# Atmega328p.net
KiCad netlist of a schematic drawn in Altium Designer
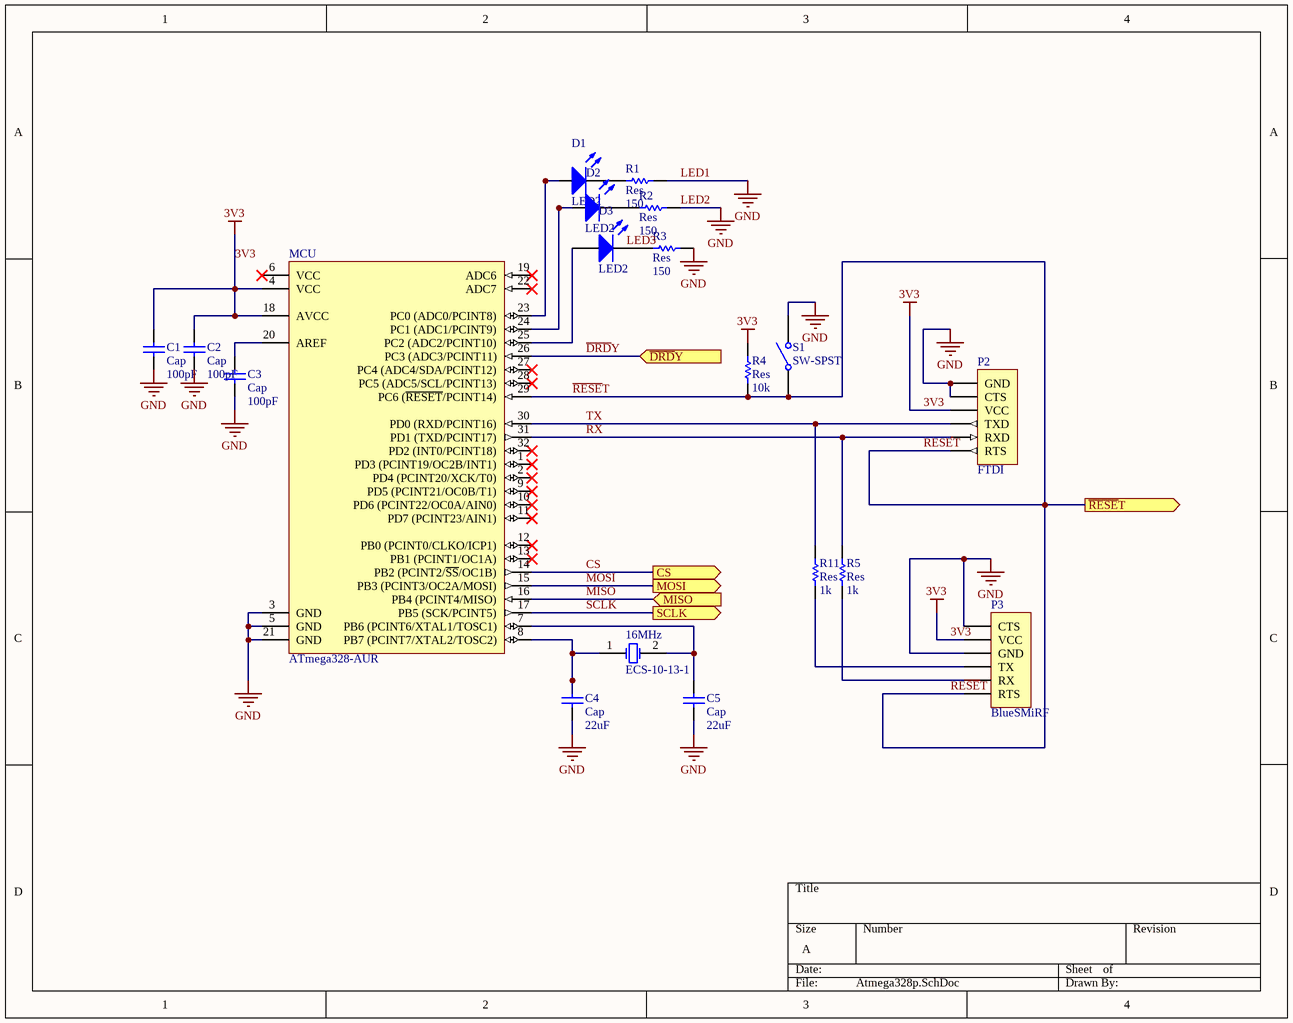
[diagram p0: Atmega328p.SchDoc]

(export (version "E")
  (design (tool "Eeschema 10.0.6"))
  (components
    (comp (ref "16MHz")
      (value "ECS-10-13-1")
      (footprint "HC-49U")
      (description "Crystal Oscillator")
      (fields (field (name "PUBLISHER") "Altium Limited"))
      (libsource (lib "ECS Crystal Oscillator") (part "ECS-10-13-1"))
    )
    (comp (ref "C1")
      (value "Cap")
      (footprint "1608[0603]")
      (description "Capacitor")
      (fields (field (name "C1") "100pF") (field (name "PUBLISHER") "Altium Limited"))
      (libsource (lib "Miscellaneous Devices") (part "Cap"))
    )
    (comp (ref "C2")
      (value "Cap")
      (footprint "1608[0603]")
      (description "Capacitor")
      (fields (field (name "C1") "100pF") (field (name "PUBLISHER") "Altium Limited"))
      (libsource (lib "Miscellaneous Devices") (part "Cap"))
    )
    (comp (ref "C3")
      (value "Cap")
      (footprint "1608[0603]")
      (description "Capacitor")
      (fields (field (name "C1") "100pF") (field (name "PUBLISHER") "Altium Limited"))
      (libsource (lib "Miscellaneous Devices") (part "Cap"))
    )
    (comp (ref "C4")
      (value "Cap")
      (footprint "1608[0603]")
      (description "Capacitor")
      (fields (field (name "ALTIUM_VALUE") "22uF") (field (name "PUBLISHER") "Altium Limited"))
      (libsource (lib "Miscellaneous Devices") (part "Cap"))
    )
    (comp (ref "C5")
      (value "Cap")
      (footprint "1608[0603]")
      (description "Capacitor")
      (fields (field (name "ALTIUM_VALUE") "22uF") (field (name "PUBLISHER") "Altium Limited"))
      (libsource (lib "Miscellaneous Devices") (part "Cap"))
    )
    (comp (ref "D1")
      (value "LED2")
      (footprint "3.2X1.6X1.1")
      (description "Typical RED, GREEN, YELLOW, AMBER GaAs LED")
      (fields (field (name "PUBLISHER") "Altium Limited"))
      (libsource (lib "Miscellaneous Devices") (part "LED2"))
    )
    (comp (ref "D2")
      (value "LED2")
      (footprint "3.2X1.6X1.1")
      (description "Typical RED, GREEN, YELLOW, AMBER GaAs LED")
      (fields (field (name "PUBLISHER") "Altium Limited"))
      (libsource (lib "Miscellaneous Devices") (part "LED2"))
    )
    (comp (ref "D3")
      (value "LED2")
      (footprint "3.2X1.6X1.1")
      (description "Typical RED, GREEN, YELLOW, AMBER GaAs LED")
      (fields (field (name "PUBLISHER") "Altium Limited"))
      (libsource (lib "Miscellaneous Devices") (part "LED2"))
    )
    (comp (ref "MCU")
      (value "ATmega328-AUR")
      (footprint "32A_N")
      (fields (field (name "PUBLISHER") "Altium Limited"))
      (libsource (lib "Atmel Microcontroller 8-Bit megaAVR") (part "ATmega328-AUR"))
    )
    (comp (ref "P2")
      (value "FTDI")
      (footprint "HDR1X6")
      (description "Header, 6-Pin")
      (fields (field (name "PUBLISHER") "Altium Limited"))
      (libsource (lib "Miscellaneous Connectors") (part "Header 6"))
    )
    (comp (ref "P3")
      (value "BlueSMiRF")
      (footprint "HDR1X6")
      (description "Header, 6-Pin")
      (fields (field (name "PUBLISHER") "Altium Limited"))
      (libsource (lib "Miscellaneous Connectors") (part "Header 6"))
    )
    (comp (ref "R1")
      (value "Res")
      (footprint "1608[0603]")
      (description "Resistor")
      (fields (field (name "ALTIUM_VALUE") "150") (field (name "PUBLISHER") "Altium Limited"))
      (libsource (lib "Miscellaneous Devices") (part "Res1"))
    )
    (comp (ref "R2")
      (value "Res")
      (footprint "1608[0603]")
      (description "Resistor")
      (fields (field (name "ALTIUM_VALUE") "150") (field (name "PUBLISHER") "Altium Limited"))
      (libsource (lib "Miscellaneous Devices") (part "Res1"))
    )
    (comp (ref "R3")
      (value "Res")
      (footprint "1608[0603]")
      (description "Resistor")
      (fields (field (name "ALTIUM_VALUE") "150") (field (name "PUBLISHER") "Altium Limited"))
      (libsource (lib "Miscellaneous Devices") (part "Res1"))
    )
    (comp (ref "R4")
      (value "Res")
      (footprint "J1-0603")
      (description "Resistor")
      (fields (field (name "ALTIUM_VALUE") "10k") (field (name "PUBLISHER") "Altium Limited"))
      (libsource (lib "Miscellaneous Devices") (part "Res1"))
    )
    (comp (ref "R5")
      (value "Res")
      (footprint "1608[0603]")
      (description "Resistor")
      (fields (field (name "ALTIUM_VALUE") "1k") (field (name "PUBLISHER") "Altium Limited"))
      (libsource (lib "Miscellaneous Devices") (part "Res1"))
    )
    (comp (ref "R11")
      (value "Res")
      (footprint "1608[0603]")
      (description "Resistor")
      (fields (field (name "ALTIUM_VALUE") "1k") (field (name "PUBLISHER") "Altium Limited"))
      (libsource (lib "Miscellaneous Devices") (part "Res1"))
    )
    (comp (ref "S1")
      (value "SW-SPST")
      (footprint "SPST-2")
      (description "Single-Pole, Single-Throw Switch")
      (fields (field (name "PUBLISHER") "Altium Limited"))
      (libsource (lib "Miscellaneous Devices") (part "SW-SPST"))
    )
  )
  (nets
    (net (code "1") (name "/CS") (class "Default")
      (node (ref "MCU") (pin "14") (pinfunction "PB2_(PCINT2/~{SS}/OC1B)_14") (pintype "output"))
    )
    (net (code "3") (name "/MISO") (class "Default")
      (node (ref "MCU") (pin "16") (pinfunction "PB4_(PCINT4/MISO)_16") (pintype "input"))
    )
    (net (code "4") (name "/MOSI") (class "Default")
      (node (ref "MCU") (pin "15") (pinfunction "PB3_(PCINT3/OC2A/MOSI)_15") (pintype "output"))
    )
    (net (code "5") (name "/RX") (class "Default")
      (node (ref "MCU") (pin "31") (pinfunction "PD1_(TXD/PCINT17)_31") (pintype "output"))
      (node (ref "P2") (pin "5") (pinfunction "RXD_5") (pintype "input"))
      (node (ref "R5") (pin "1") (pinfunction "1_1") (pintype "passive"))
    )
    (net (code "6") (name "/SCLK") (class "Default")
      (node (ref "MCU") (pin "17") (pinfunction "PB5_(SCK/PCINT5)_17") (pintype "output"))
    )
    (net (code "7") (name "/TX") (class "Default")
      (node (ref "MCU") (pin "30") (pinfunction "PD0_(RXD/PCINT16)_30") (pintype "input"))
      (node (ref "P2") (pin "4") (pinfunction "TXD_4") (pintype "output"))
      (node (ref "R11") (pin "1") (pinfunction "1_1") (pintype "passive"))
    )
    (net (code "8") (name "/~{DRD}Y") (class "Default")
      (node (ref "MCU") (pin "26") (pinfunction "PC3_(ADC3/PCINT11)_26") (pintype "input"))
    )
    (net (code "9") (name "/~{RESE}T") (class "Default")
      (node (ref "MCU") (pin "29") (pinfunction "PC6_(~{RESET}/PCINT14)_29") (pintype "input"))
      (node (ref "P2") (pin "6") (pinfunction "RTS_6") (pintype "output"))
      (node (ref "P3") (pin "6") (pinfunction "RTS_6") (pintype "output"))
      (node (ref "R4") (pin "1") (pinfunction "1_1") (pintype "passive"))
      (node (ref "S1") (pin "1") (pinfunction "COMMON_1") (pintype "passive"))
    )
    (net (code "10") (name "3V3") (class "Default")
      (node (ref "C1") (pin "2") (pinfunction "2_2") (pintype "passive"))
      (node (ref "C2") (pin "2") (pinfunction "2_2") (pintype "passive"))
      (node (ref "MCU") (pin "18") (pinfunction "AVCC_18") (pintype "power_in"))
      (node (ref "MCU") (pin "4") (pinfunction "VCC_4") (pintype "power_in"))
      (node (ref "P2") (pin "3") (pinfunction "VCC_3") (pintype "power_in"))
      (node (ref "P3") (pin "2") (pinfunction "CTS_2") (pintype "passive"))
      (node (ref "R4") (pin "2") (pinfunction "2_2") (pintype "passive"))
    )
    (net (code "11") (name "GND") (class "Default")
      (node (ref "C1") (pin "1") (pinfunction "1_1") (pintype "passive"))
      (node (ref "C2") (pin "1") (pinfunction "1_1") (pintype "passive"))
      (node (ref "C3") (pin "1") (pinfunction "1_1") (pintype "passive"))
      (node (ref "C4") (pin "1") (pinfunction "1_1") (pintype "passive"))
      (node (ref "C5") (pin "1") (pinfunction "1_1") (pintype "passive"))
      (node (ref "MCU") (pin "21") (pinfunction "GND_21") (pintype "power_in"))
      (node (ref "MCU") (pin "3") (pinfunction "GND_3") (pintype "power_in"))
      (node (ref "MCU") (pin "5") (pinfunction "GND_5") (pintype "power_in"))
      (node (ref "P2") (pin "1") (pinfunction "GND_1") (pintype "power_in"))
      (node (ref "P2") (pin "2") (pinfunction "CTS_2") (pintype "passive"))
      (node (ref "P3") (pin "1") (pinfunction "GND_1") (pintype "power_in"))
      (node (ref "P3") (pin "3") (pinfunction "VCC_3") (pintype "power_in"))
      (node (ref "R1") (pin "1") (pinfunction "1_1") (pintype "passive"))
      (node (ref "R2") (pin "1") (pinfunction "1_1") (pintype "passive"))
      (node (ref "R3") (pin "1") (pinfunction "1_1") (pintype "passive"))
      (node (ref "S1") (pin "2") (pinfunction "NO_2") (pintype "passive"))
    )
    (net (code "12") (name "Net-(16MHz-OSC1)") (class "Default")
      (node (ref "16MHz") (pin "1") (pinfunction "OSC1_1") (pintype "passive"))
      (node (ref "C4") (pin "2") (pinfunction "2_2") (pintype "passive"))
      (node (ref "MCU") (pin "8") (pinfunction "PB7_(PCINT7/XTAL2/TOSC2)_8") (pintype "bidirectional"))
    )
    (net (code "13") (name "Net-(16MHz-OSC2)") (class "Default")
      (node (ref "16MHz") (pin "2") (pinfunction "OSC2_2") (pintype "passive"))
      (node (ref "C5") (pin "2") (pinfunction "2_2") (pintype "passive"))
      (node (ref "MCU") (pin "7") (pinfunction "PB6_(PCINT6/XTAL1/TOSC1)_7") (pintype "bidirectional"))
    )
    (net (code "14") (name "Net-(D1-A)") (class "Default")
      (node (ref "D1") (pin "1") (pinfunction "A_1") (pintype "passive"))
      (node (ref "MCU") (pin "23") (pinfunction "PC0_(ADC0/PCINT8)_23") (pintype "bidirectional"))
    )
    (net (code "15") (name "Net-(D1-K)") (class "Default")
      (node (ref "D1") (pin "2") (pinfunction "K_2") (pintype "passive"))
      (node (ref "R1") (pin "2") (pinfunction "2_2") (pintype "passive"))
    )
    (net (code "16") (name "Net-(D2-A)") (class "Default")
      (node (ref "D2") (pin "1") (pinfunction "A_1") (pintype "passive"))
      (node (ref "MCU") (pin "24") (pinfunction "PC1_(ADC1/PCINT9)_24") (pintype "bidirectional"))
    )
    (net (code "17") (name "Net-(D2-K)") (class "Default")
      (node (ref "D2") (pin "2") (pinfunction "K_2") (pintype "passive"))
      (node (ref "R2") (pin "2") (pinfunction "2_2") (pintype "passive"))
    )
    (net (code "18") (name "Net-(D3-A)") (class "Default")
      (node (ref "D3") (pin "1") (pinfunction "A_1") (pintype "passive"))
      (node (ref "MCU") (pin "25") (pinfunction "PC2_(ADC2/PCINT10)_25") (pintype "bidirectional"))
    )
    (net (code "19") (name "Net-(D3-K)") (class "Default")
      (node (ref "D3") (pin "2") (pinfunction "K_2") (pintype "passive"))
      (node (ref "R3") (pin "2") (pinfunction "2_2") (pintype "passive"))
    )
    (net (code "20") (name "Net-(MCU-AREF)") (class "Default")
      (node (ref "C3") (pin "2") (pinfunction "2_2") (pintype "passive"))
      (node (ref "MCU") (pin "20") (pinfunction "AREF_20") (pintype "passive"))
    )
    (net (code "21") (name "Net-(P3-RXD)") (class "Default")
      (node (ref "P3") (pin "5") (pinfunction "RXD_5") (pintype "input"))
      (node (ref "R5") (pin "2") (pinfunction "2_2") (pintype "passive"))
    )
    (net (code "22") (name "Net-(P3-TXD)") (class "Default")
      (node (ref "P3") (pin "4") (pinfunction "TXD_4") (pintype "output"))
      (node (ref "R11") (pin "2") (pinfunction "2_2") (pintype "passive"))
    )
    (net (code "23") (name "unconnected-(MCU-ADC6-Pad19)") (class "Default")
      (node (ref "MCU") (pin "19") (pinfunction "ADC6_19") (pintype "input+no_connect"))
    )
    (net (code "24") (name "unconnected-(MCU-ADC7-Pad22)") (class "Default")
      (node (ref "MCU") (pin "22") (pinfunction "ADC7_22") (pintype "input+no_connect"))
    )
    (net (code "25") (name "unconnected-(MCU-PB0_(PCINT0{slash}CLKO{slash}ICP1)-Pad12)") (class "Default")
      (node (ref "MCU") (pin "12") (pinfunction "PB0_(PCINT0/CLKO/ICP1)_12") (pintype "bidirectional+no_connect"))
    )
    (net (code "26") (name "unconnected-(MCU-PB1_(PCINT1{slash}OC1A)-Pad13)") (class "Default")
      (node (ref "MCU") (pin "13") (pinfunction "PB1_(PCINT1/OC1A)_13") (pintype "bidirectional+no_connect"))
    )
    (net (code "27") (name "unconnected-(MCU-PC4_(ADC4{slash}SDA{slash}PCINT12)-Pad27)") (class "Default")
      (node (ref "MCU") (pin "27") (pinfunction "PC4_(ADC4/SDA/PCINT12)_27") (pintype "bidirectional+no_connect"))
    )
    (net (code "28") (name "unconnected-(MCU-PC5_(ADC5{slash}SCL{slash}PCINT13)-Pad28)") (class "Default")
      (node (ref "MCU") (pin "28") (pinfunction "PC5_(ADC5/SCL/PCINT13)_28") (pintype "bidirectional+no_connect"))
    )
    (net (code "29") (name "unconnected-(MCU-PD2_(INT0{slash}PCINT18)-Pad32)") (class "Default")
      (node (ref "MCU") (pin "32") (pinfunction "PD2_(INT0/PCINT18)_32") (pintype "bidirectional+no_connect"))
    )
    (net (code "30") (name "unconnected-(MCU-PD3_(PCINT19{slash}OC2B{slash}INT1)-Pad1)") (class "Default")
      (node (ref "MCU") (pin "1") (pinfunction "PD3_(PCINT19/OC2B/INT1)_1") (pintype "bidirectional+no_connect"))
    )
    (net (code "31") (name "unconnected-(MCU-PD4_(PCINT20{slash}XCK{slash}T0)-Pad2)") (class "Default")
      (node (ref "MCU") (pin "2") (pinfunction "PD4_(PCINT20/XCK/T0)_2") (pintype "bidirectional+no_connect"))
    )
    (net (code "32") (name "unconnected-(MCU-PD5_(PCINT21{slash}OC0B{slash}T1)-Pad9)") (class "Default")
      (node (ref "MCU") (pin "9") (pinfunction "PD5_(PCINT21/OC0B/T1)_9") (pintype "bidirectional+no_connect"))
    )
    (net (code "33") (name "unconnected-(MCU-PD6_(PCINT22{slash}OC0A{slash}AIN0)-Pad10)") (class "Default")
      (node (ref "MCU") (pin "10") (pinfunction "PD6_(PCINT22/OC0A/AIN0)_10") (pintype "bidirectional+no_connect"))
    )
    (net (code "34") (name "unconnected-(MCU-PD7_(PCINT23{slash}AIN1)-Pad11)") (class "Default")
      (node (ref "MCU") (pin "11") (pinfunction "PD7_(PCINT23/AIN1)_11") (pintype "bidirectional+no_connect"))
    )
    (net (code "35") (name "unconnected-(MCU-VCC-Pad6)") (class "Default")
      (node (ref "MCU") (pin "6") (pinfunction "VCC_6") (pintype "power_in+no_connect"))
    )
  )
)
